# mega128.net
KiCad netlist of a schematic drawn in EAGLE
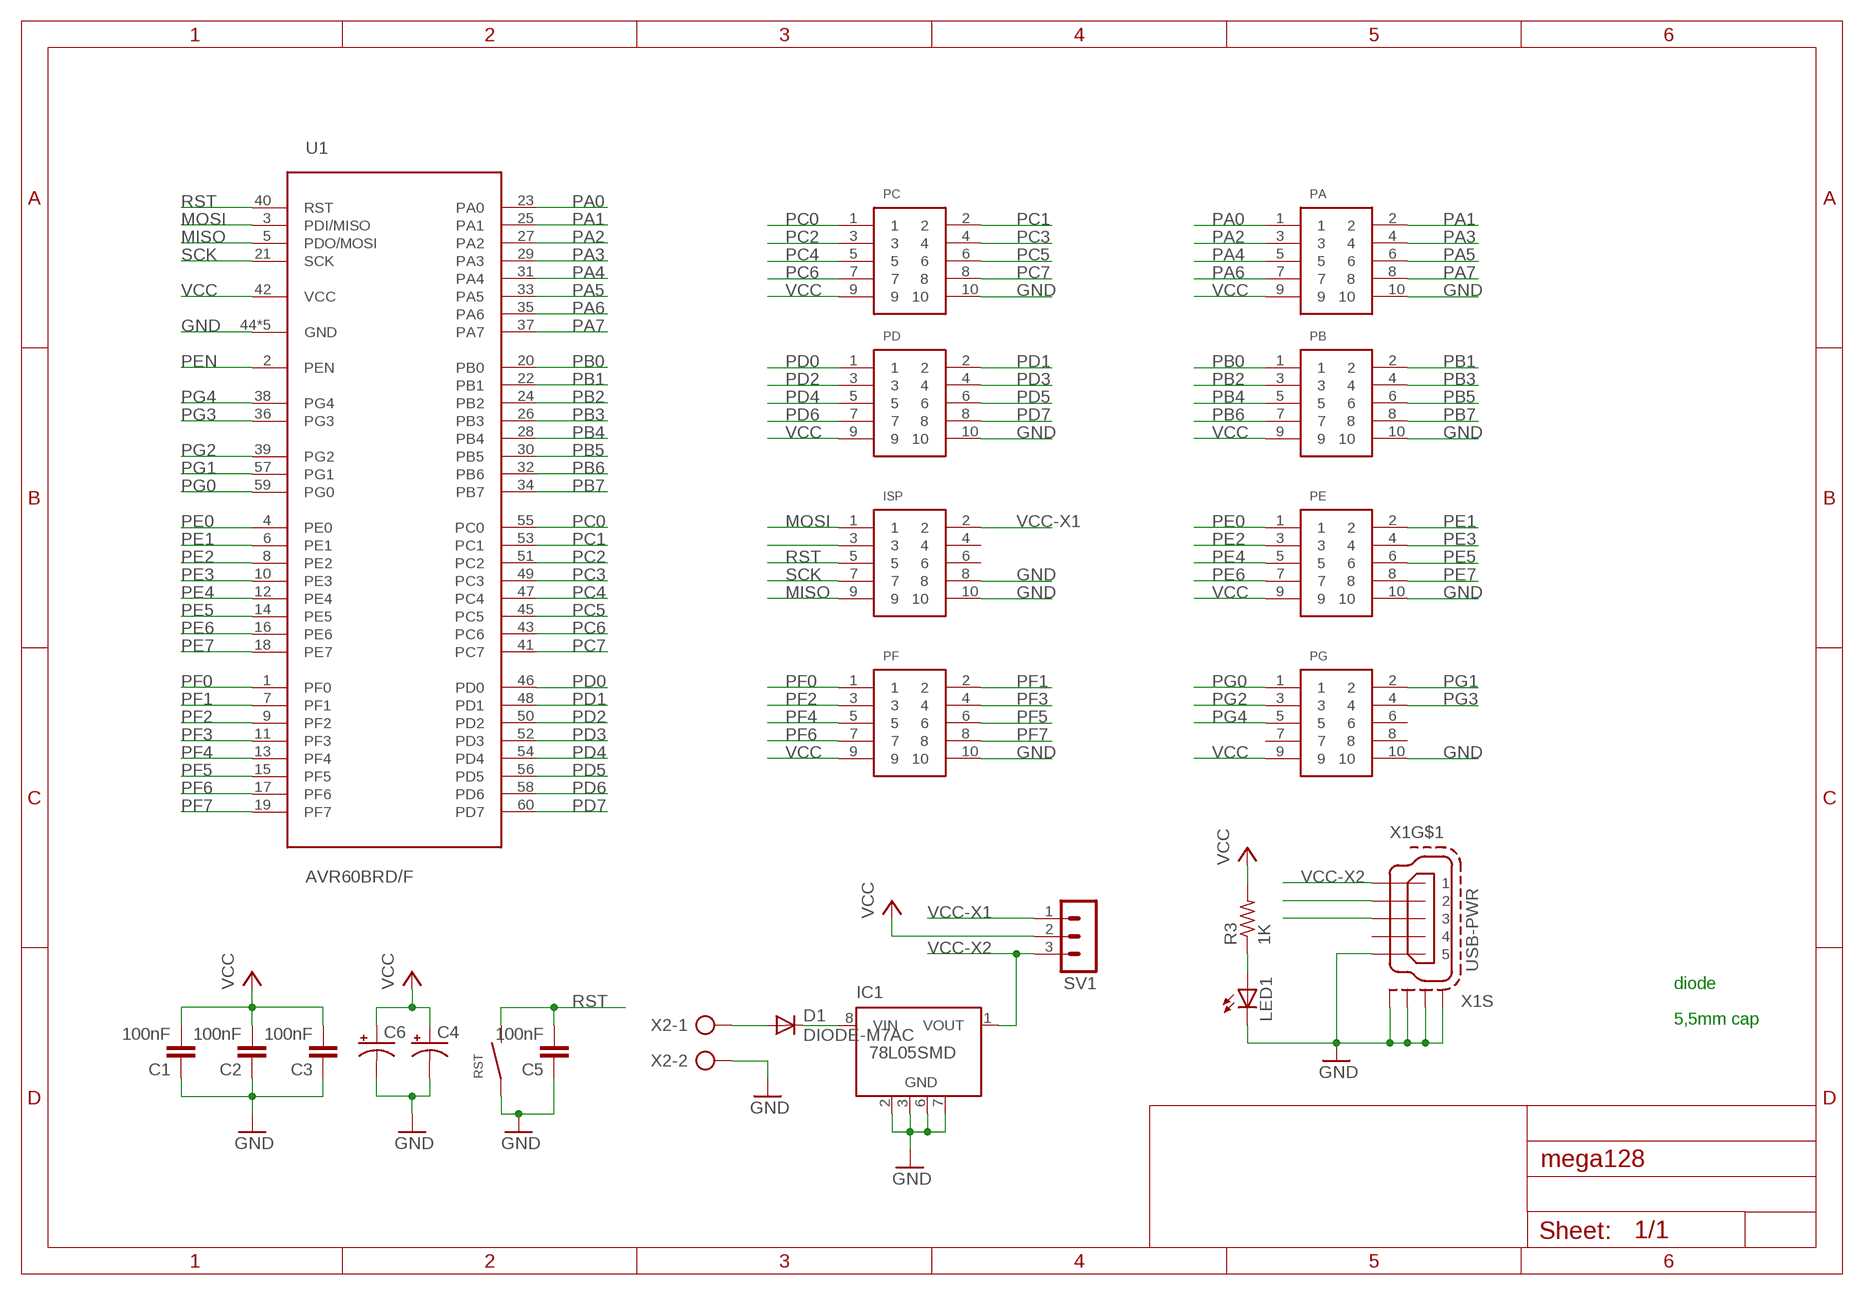
[diagram p0: schematic, sheet 1]

(export (version "E")
  (design (tool "Eeschema 10.0.6"))
  (components
    (comp (ref "C1")
      (value "100nF")
      (footprint "eagle-import:C0805")
      (libsource (lib "eagle-import") (part "C-EUC0805"))
    )
    (comp (ref "C2")
      (value "100nF")
      (footprint "eagle-import:C0805")
      (libsource (lib "eagle-import") (part "C-EUC0805"))
    )
    (comp (ref "C3")
      (value "100nF")
      (footprint "eagle-import:C0805")
      (libsource (lib "eagle-import") (part "C-EUC0805"))
    )
    (comp (ref "C4")
      (value "CPOL-US085CS-1AR")
      (footprint "eagle-import:085CS_1AR")
      (libsource (lib "eagle-import") (part "CPOL-US085CS-1AR"))
    )
    (comp (ref "C5")
      (value "100nF")
      (footprint "eagle-import:C0805")
      (libsource (lib "eagle-import") (part "C-EUC0805"))
    )
    (comp (ref "C6")
      (value "CPOL-US085CS-1AR")
      (footprint "eagle-import:085CS_1AR")
      (libsource (lib "eagle-import") (part "CPOL-US085CS-1AR"))
    )
    (comp (ref "D1")
      (value "DIODE-M7AC")
      (footprint "eagle-import:M7")
      (libsource (lib "eagle-import") (part "DIODE-M7AC"))
    )
    (comp (ref "IC1")
      (value "78L05SMD")
      (footprint "eagle-import:SO08")
      (libsource (lib "eagle-import") (part "78LSMD05"))
    )
    (comp (ref "ISP")
      (value "IDC-SOCK")
      (footprint "eagle-import:IDC-SOCK")
      (libsource (lib "eagle-import") (part "IDC-SOCK"))
    )
    (comp (ref "LED1")
      (value "LEDSML0805")
      (footprint "eagle-import:SML0805")
      (libsource (lib "eagle-import") (part "LEDSML0805"))
    )
    (comp (ref "PA")
      (value "IDC-SOCK")
      (footprint "eagle-import:IDC-SOCK")
      (libsource (lib "eagle-import") (part "IDC-SOCK"))
    )
    (comp (ref "PB")
      (value "IDC-SOCK")
      (footprint "eagle-import:IDC-SOCK")
      (libsource (lib "eagle-import") (part "IDC-SOCK"))
    )
    (comp (ref "PC")
      (value "IDC-SOCK")
      (footprint "eagle-import:IDC-SOCK")
      (libsource (lib "eagle-import") (part "IDC-SOCK"))
    )
    (comp (ref "PD")
      (value "IDC-SOCK")
      (footprint "eagle-import:IDC-SOCK")
      (libsource (lib "eagle-import") (part "IDC-SOCK"))
    )
    (comp (ref "PE")
      (value "IDC-SOCK")
      (footprint "eagle-import:IDC-SOCK")
      (libsource (lib "eagle-import") (part "IDC-SOCK"))
    )
    (comp (ref "PF")
      (value "IDC-SOCK")
      (footprint "eagle-import:IDC-SOCK")
      (libsource (lib "eagle-import") (part "IDC-SOCK"))
    )
    (comp (ref "PG")
      (value "IDC-SOCK")
      (footprint "eagle-import:IDC-SOCK")
      (libsource (lib "eagle-import") (part "IDC-SOCK"))
    )
    (comp (ref "R3")
      (value "1K")
      (footprint "eagle-import:R0805")
      (libsource (lib "eagle-import") (part "R-US_R0805"))
    )
    (comp (ref "RST")
      (value "SMD-BTN")
      (footprint "eagle-import:SMD-BTN")
      (libsource (lib "eagle-import") (part "SMD-BTN"))
    )
    (comp (ref "SV1")
      (value "MA03-1")
      (footprint "eagle-import:MA03-1")
      (libsource (lib "eagle-import") (part "MA03-1"))
    )
    (comp (ref "U1")
      (value "AVR60BRD/F")
      (footprint "eagle-import:AVR60-BRD")
      (libsource (lib "eagle-import") (part "AVR60BRD/F"))
    )
    (comp (ref "X1")
      (value "USB-PWR")
      (footprint "eagle-import:32005-201")
      (libsource (lib "eagle-import") (part "MINI-USB-SCHIELD-32005-201"))
    )
    (comp (ref "X2")
      (value "AK300/2")
      (footprint "eagle-import:AK300_2")
      (libsource (lib "eagle-import") (part "AK300/2"))
    )
  )
  (nets
    (net (code "1") (name "/MISO") (class "Default")
      (node (ref "ISP") (pin "9") (pinfunction "9_9") (pintype "bidirectional"))
      (node (ref "U1") (pin "5") (pinfunction "PDO/MOSI_5") (pintype "bidirectional"))
    )
    (net (code "2") (name "/MOSI") (class "Default")
      (node (ref "ISP") (pin "1") (pinfunction "1_1") (pintype "bidirectional"))
      (node (ref "U1") (pin "3") (pinfunction "PDI/MISO_3") (pintype "bidirectional"))
    )
    (net (code "3") (name "/PA0") (class "Default")
      (node (ref "PA") (pin "1") (pinfunction "1_1") (pintype "bidirectional"))
      (node (ref "U1") (pin "23") (pinfunction "PA0_23") (pintype "bidirectional"))
    )
    (net (code "4") (name "/PA1") (class "Default")
      (node (ref "PA") (pin "2") (pinfunction "2_2") (pintype "bidirectional"))
      (node (ref "U1") (pin "25") (pinfunction "PA1_25") (pintype "bidirectional"))
    )
    (net (code "5") (name "/PA2") (class "Default")
      (node (ref "PA") (pin "3") (pinfunction "3_3") (pintype "bidirectional"))
      (node (ref "U1") (pin "27") (pinfunction "PA2_27") (pintype "bidirectional"))
    )
    (net (code "6") (name "/PA3") (class "Default")
      (node (ref "PA") (pin "4") (pinfunction "4_4") (pintype "bidirectional"))
      (node (ref "U1") (pin "29") (pinfunction "PA3_29") (pintype "bidirectional"))
    )
    (net (code "7") (name "/PA4") (class "Default")
      (node (ref "PA") (pin "5") (pinfunction "5_5") (pintype "bidirectional"))
      (node (ref "U1") (pin "31") (pinfunction "PA4_31") (pintype "bidirectional"))
    )
    (net (code "8") (name "/PA5") (class "Default")
      (node (ref "PA") (pin "6") (pinfunction "6_6") (pintype "bidirectional"))
      (node (ref "U1") (pin "33") (pinfunction "PA5_33") (pintype "bidirectional"))
    )
    (net (code "9") (name "/PA6") (class "Default")
      (node (ref "PA") (pin "7") (pinfunction "7_7") (pintype "bidirectional"))
      (node (ref "U1") (pin "35") (pinfunction "PA6_35") (pintype "bidirectional"))
    )
    (net (code "10") (name "/PA7") (class "Default")
      (node (ref "PA") (pin "8") (pinfunction "8_8") (pintype "bidirectional"))
      (node (ref "U1") (pin "37") (pinfunction "PA7_37") (pintype "bidirectional"))
    )
    (net (code "11") (name "/PB0") (class "Default")
      (node (ref "PB") (pin "1") (pinfunction "1_1") (pintype "bidirectional"))
      (node (ref "U1") (pin "20") (pinfunction "PB0_20") (pintype "bidirectional"))
    )
    (net (code "12") (name "/PB1") (class "Default")
      (node (ref "PB") (pin "2") (pinfunction "2_2") (pintype "bidirectional"))
      (node (ref "U1") (pin "22") (pinfunction "PB1_22") (pintype "bidirectional"))
    )
    (net (code "13") (name "/PB2") (class "Default")
      (node (ref "PB") (pin "3") (pinfunction "3_3") (pintype "bidirectional"))
      (node (ref "U1") (pin "24") (pinfunction "PB2_24") (pintype "bidirectional"))
    )
    (net (code "14") (name "/PB3") (class "Default")
      (node (ref "PB") (pin "4") (pinfunction "4_4") (pintype "bidirectional"))
      (node (ref "U1") (pin "26") (pinfunction "PB3_26") (pintype "bidirectional"))
    )
    (net (code "15") (name "/PB4") (class "Default")
      (node (ref "PB") (pin "5") (pinfunction "5_5") (pintype "bidirectional"))
      (node (ref "U1") (pin "28") (pinfunction "PB4_28") (pintype "bidirectional"))
    )
    (net (code "16") (name "/PB5") (class "Default")
      (node (ref "PB") (pin "6") (pinfunction "6_6") (pintype "bidirectional"))
      (node (ref "U1") (pin "30") (pinfunction "PB5_30") (pintype "bidirectional"))
    )
    (net (code "17") (name "/PB6") (class "Default")
      (node (ref "PB") (pin "7") (pinfunction "7_7") (pintype "bidirectional"))
      (node (ref "U1") (pin "32") (pinfunction "PB6_32") (pintype "bidirectional"))
    )
    (net (code "18") (name "/PB7") (class "Default")
      (node (ref "PB") (pin "8") (pinfunction "8_8") (pintype "bidirectional"))
      (node (ref "U1") (pin "34") (pinfunction "PB7_34") (pintype "bidirectional"))
    )
    (net (code "19") (name "/PC0") (class "Default")
      (node (ref "PC") (pin "1") (pinfunction "1_1") (pintype "bidirectional"))
      (node (ref "U1") (pin "55") (pinfunction "PC0_55") (pintype "bidirectional"))
    )
    (net (code "20") (name "/PC1") (class "Default")
      (node (ref "PC") (pin "2") (pinfunction "2_2") (pintype "bidirectional"))
      (node (ref "U1") (pin "53") (pinfunction "PC1_53") (pintype "bidirectional"))
    )
    (net (code "21") (name "/PC2") (class "Default")
      (node (ref "PC") (pin "3") (pinfunction "3_3") (pintype "bidirectional"))
      (node (ref "U1") (pin "51") (pinfunction "PC2_51") (pintype "bidirectional"))
    )
    (net (code "22") (name "/PC3") (class "Default")
      (node (ref "PC") (pin "4") (pinfunction "4_4") (pintype "bidirectional"))
      (node (ref "U1") (pin "49") (pinfunction "PC3_49") (pintype "bidirectional"))
    )
    (net (code "23") (name "/PC4") (class "Default")
      (node (ref "PC") (pin "5") (pinfunction "5_5") (pintype "bidirectional"))
      (node (ref "U1") (pin "47") (pinfunction "PC4_47") (pintype "bidirectional"))
    )
    (net (code "24") (name "/PC5") (class "Default")
      (node (ref "PC") (pin "6") (pinfunction "6_6") (pintype "bidirectional"))
      (node (ref "U1") (pin "45") (pinfunction "PC5_45") (pintype "bidirectional"))
    )
    (net (code "25") (name "/PC6") (class "Default")
      (node (ref "PC") (pin "7") (pinfunction "7_7") (pintype "bidirectional"))
      (node (ref "U1") (pin "43") (pinfunction "PC6_43") (pintype "bidirectional"))
    )
    (net (code "26") (name "/PC7") (class "Default")
      (node (ref "PC") (pin "8") (pinfunction "8_8") (pintype "bidirectional"))
      (node (ref "U1") (pin "41") (pinfunction "PC7_41") (pintype "bidirectional"))
    )
    (net (code "27") (name "/PD0") (class "Default")
      (node (ref "PD") (pin "1") (pinfunction "1_1") (pintype "bidirectional"))
      (node (ref "U1") (pin "46") (pinfunction "PD0_46") (pintype "bidirectional"))
    )
    (net (code "28") (name "/PD1") (class "Default")
      (node (ref "PD") (pin "2") (pinfunction "2_2") (pintype "bidirectional"))
      (node (ref "U1") (pin "48") (pinfunction "PD1_48") (pintype "bidirectional"))
    )
    (net (code "29") (name "/PD2") (class "Default")
      (node (ref "PD") (pin "3") (pinfunction "3_3") (pintype "bidirectional"))
      (node (ref "U1") (pin "50") (pinfunction "PD2_50") (pintype "bidirectional"))
    )
    (net (code "30") (name "/PD3") (class "Default")
      (node (ref "PD") (pin "4") (pinfunction "4_4") (pintype "bidirectional"))
      (node (ref "U1") (pin "52") (pinfunction "PD3_52") (pintype "bidirectional"))
    )
    (net (code "31") (name "/PD4") (class "Default")
      (node (ref "PD") (pin "5") (pinfunction "5_5") (pintype "bidirectional"))
      (node (ref "U1") (pin "54") (pinfunction "PD4_54") (pintype "bidirectional"))
    )
    (net (code "32") (name "/PD5") (class "Default")
      (node (ref "PD") (pin "6") (pinfunction "6_6") (pintype "bidirectional"))
      (node (ref "U1") (pin "56") (pinfunction "PD5_56") (pintype "bidirectional"))
    )
    (net (code "33") (name "/PD6") (class "Default")
      (node (ref "PD") (pin "7") (pinfunction "7_7") (pintype "bidirectional"))
      (node (ref "U1") (pin "58") (pinfunction "PD6_58") (pintype "bidirectional"))
    )
    (net (code "34") (name "/PD7") (class "Default")
      (node (ref "PD") (pin "8") (pinfunction "8_8") (pintype "bidirectional"))
      (node (ref "U1") (pin "60") (pinfunction "PD7_60") (pintype "bidirectional"))
    )
    (net (code "35") (name "/PE0") (class "Default")
      (node (ref "PE") (pin "1") (pinfunction "1_1") (pintype "bidirectional"))
      (node (ref "U1") (pin "4") (pinfunction "PE0_4") (pintype "bidirectional"))
    )
    (net (code "36") (name "/PE1") (class "Default")
      (node (ref "PE") (pin "2") (pinfunction "2_2") (pintype "bidirectional"))
      (node (ref "U1") (pin "6") (pinfunction "PE1_6") (pintype "bidirectional"))
    )
    (net (code "37") (name "/PE2") (class "Default")
      (node (ref "PE") (pin "3") (pinfunction "3_3") (pintype "bidirectional"))
      (node (ref "U1") (pin "8") (pinfunction "PE2_8") (pintype "bidirectional"))
    )
    (net (code "38") (name "/PE3") (class "Default")
      (node (ref "PE") (pin "4") (pinfunction "4_4") (pintype "bidirectional"))
      (node (ref "U1") (pin "10") (pinfunction "PE3_10") (pintype "bidirectional"))
    )
    (net (code "39") (name "/PE4") (class "Default")
      (node (ref "PE") (pin "5") (pinfunction "5_5") (pintype "bidirectional"))
      (node (ref "U1") (pin "12") (pinfunction "PE4_12") (pintype "bidirectional"))
    )
    (net (code "40") (name "/PE5") (class "Default")
      (node (ref "PE") (pin "6") (pinfunction "6_6") (pintype "bidirectional"))
      (node (ref "U1") (pin "14") (pinfunction "PE5_14") (pintype "bidirectional"))
    )
    (net (code "41") (name "/PE6") (class "Default")
      (node (ref "PE") (pin "7") (pinfunction "7_7") (pintype "bidirectional"))
      (node (ref "U1") (pin "16") (pinfunction "PE6_16") (pintype "bidirectional"))
    )
    (net (code "42") (name "/PE7") (class "Default")
      (node (ref "PE") (pin "8") (pinfunction "8_8") (pintype "bidirectional"))
      (node (ref "U1") (pin "18") (pinfunction "PE7_18") (pintype "bidirectional"))
    )
    (net (code "43") (name "/PEN") (class "Default")
      (node (ref "U1") (pin "2") (pinfunction "PEN_2") (pintype "bidirectional"))
    )
    (net (code "44") (name "/PF0") (class "Default")
      (node (ref "PF") (pin "1") (pinfunction "1_1") (pintype "bidirectional"))
      (node (ref "U1") (pin "1") (pinfunction "PF0_1") (pintype "bidirectional"))
    )
    (net (code "45") (name "/PF1") (class "Default")
      (node (ref "PF") (pin "2") (pinfunction "2_2") (pintype "bidirectional"))
      (node (ref "U1") (pin "7") (pinfunction "PF1_7") (pintype "bidirectional"))
    )
    (net (code "46") (name "/PF2") (class "Default")
      (node (ref "PF") (pin "3") (pinfunction "3_3") (pintype "bidirectional"))
      (node (ref "U1") (pin "9") (pinfunction "PF2_9") (pintype "bidirectional"))
    )
    (net (code "47") (name "/PF3") (class "Default")
      (node (ref "PF") (pin "4") (pinfunction "4_4") (pintype "bidirectional"))
      (node (ref "U1") (pin "11") (pinfunction "PF3_11") (pintype "bidirectional"))
    )
    (net (code "48") (name "/PF4") (class "Default")
      (node (ref "PF") (pin "5") (pinfunction "5_5") (pintype "bidirectional"))
      (node (ref "U1") (pin "13") (pinfunction "PF4_13") (pintype "bidirectional"))
    )
    (net (code "49") (name "/PF5") (class "Default")
      (node (ref "PF") (pin "6") (pinfunction "6_6") (pintype "bidirectional"))
      (node (ref "U1") (pin "15") (pinfunction "PF5_15") (pintype "bidirectional"))
    )
    (net (code "50") (name "/PF6") (class "Default")
      (node (ref "PF") (pin "7") (pinfunction "7_7") (pintype "bidirectional"))
      (node (ref "U1") (pin "17") (pinfunction "PF6_17") (pintype "bidirectional"))
    )
    (net (code "51") (name "/PF7") (class "Default")
      (node (ref "PF") (pin "8") (pinfunction "8_8") (pintype "bidirectional"))
      (node (ref "U1") (pin "19") (pinfunction "PF7_19") (pintype "bidirectional"))
    )
    (net (code "52") (name "/PG0") (class "Default")
      (node (ref "PG") (pin "1") (pinfunction "1_1") (pintype "bidirectional"))
      (node (ref "U1") (pin "59") (pinfunction "PG0_59") (pintype "bidirectional"))
    )
    (net (code "53") (name "/PG1") (class "Default")
      (node (ref "PG") (pin "2") (pinfunction "2_2") (pintype "bidirectional"))
      (node (ref "U1") (pin "57") (pinfunction "PG1_57") (pintype "bidirectional"))
    )
    (net (code "54") (name "/PG2") (class "Default")
      (node (ref "PG") (pin "3") (pinfunction "3_3") (pintype "bidirectional"))
      (node (ref "U1") (pin "39") (pinfunction "PG2_39") (pintype "bidirectional"))
    )
    (net (code "55") (name "/PG3") (class "Default")
      (node (ref "PG") (pin "4") (pinfunction "4_4") (pintype "bidirectional"))
      (node (ref "U1") (pin "36") (pinfunction "PG3_36") (pintype "bidirectional"))
    )
    (net (code "56") (name "/PG4") (class "Default")
      (node (ref "PG") (pin "5") (pinfunction "5_5") (pintype "bidirectional"))
      (node (ref "U1") (pin "38") (pinfunction "PG4_38") (pintype "bidirectional"))
    )
    (net (code "57") (name "/RST") (class "Default")
      (node (ref "C5") (pin "2") (pinfunction "2_2") (pintype "passive"))
      (node (ref "ISP") (pin "5") (pinfunction "5_5") (pintype "bidirectional"))
      (node (ref "RST") (pin "2") (pinfunction "P$2_2") (pintype "bidirectional"))
      (node (ref "U1") (pin "40") (pinfunction "RST_40") (pintype "bidirectional"))
    )
    (net (code "58") (name "/SCK") (class "Default")
      (node (ref "ISP") (pin "7") (pinfunction "7_7") (pintype "bidirectional"))
      (node (ref "U1") (pin "21") (pinfunction "SCK_21") (pintype "bidirectional"))
    )
    (net (code "59") (name "/VCC-X1") (class "Default")
      (node (ref "ISP") (pin "2") (pinfunction "2_2") (pintype "bidirectional"))
      (node (ref "SV1") (pin "1") (pinfunction "1_1") (pintype "passive"))
    )
    (net (code "60") (name "/VCC-X2") (class "Default")
      (node (ref "IC1") (pin "1") (pinfunction "VOUT_1") (pintype "output"))
      (node (ref "SV1") (pin "3") (pinfunction "3_3") (pintype "passive"))
      (node (ref "X1") (pin "1") (pinfunction "1_1") (pintype "passive"))
    )
    (net (code "61") (name "GND") (class "Default")
      (node (ref "C1") (pin "1") (pinfunction "1_1") (pintype "passive"))
      (node (ref "C2") (pin "1") (pinfunction "1_1") (pintype "passive"))
      (node (ref "C3") (pin "1") (pinfunction "1_1") (pintype "passive"))
      (node (ref "C4") (pin "-") (pinfunction "-_-") (pintype "passive"))
      (node (ref "C5") (pin "1") (pinfunction "1_1") (pintype "passive"))
      (node (ref "C6") (pin "-") (pinfunction "-_-") (pintype "passive"))
      (node (ref "IC1") (pin "2") (pinfunction "GND_2") (pintype "power_in"))
      (node (ref "IC1") (pin "3") (pinfunction "GND_3") (pintype "power_in"))
      (node (ref "IC1") (pin "6") (pinfunction "GND_6") (pintype "power_in"))
      (node (ref "IC1") (pin "7") (pinfunction "GND_7") (pintype "power_in"))
      (node (ref "ISP") (pin "10") (pinfunction "10_10") (pintype "bidirectional"))
      (node (ref "ISP") (pin "8") (pinfunction "8_8") (pintype "bidirectional"))
      (node (ref "LED1") (pin "C") (pinfunction "C_C") (pintype "passive"))
      (node (ref "PA") (pin "10") (pinfunction "10_10") (pintype "bidirectional"))
      (node (ref "PB") (pin "10") (pinfunction "10_10") (pintype "bidirectional"))
      (node (ref "PC") (pin "10") (pinfunction "10_10") (pintype "bidirectional"))
      (node (ref "PD") (pin "10") (pinfunction "10_10") (pintype "bidirectional"))
      (node (ref "PE") (pin "10") (pinfunction "10_10") (pintype "bidirectional"))
      (node (ref "PF") (pin "10") (pinfunction "10_10") (pintype "bidirectional"))
      (node (ref "PG") (pin "10") (pinfunction "10_10") (pintype "bidirectional"))
      (node (ref "RST") (pin "1") (pinfunction "P$1_1") (pintype "bidirectional"))
      (node (ref "U1") (pin "44") (pinfunction "GND_44") (pintype "bidirectional"))
      (node (ref "U1") (pin "61") (pinfunction "GND_61") (pintype "bidirectional"))
      (node (ref "U1") (pin "62") (pinfunction "GND_62") (pintype "bidirectional"))
      (node (ref "U1") (pin "63") (pinfunction "GND_63") (pintype "bidirectional"))
      (node (ref "U1") (pin "64") (pinfunction "GND_64") (pintype "bidirectional"))
      (node (ref "X1") (pin "5") (pinfunction "5_5") (pintype "passive"))
      (node (ref "X1") (pin "M1") (pinfunction "S1_M1") (pintype "passive"))
      (node (ref "X1") (pin "M2") (pinfunction "S2_M2") (pintype "passive"))
      (node (ref "X1") (pin "M3") (pinfunction "S3_M3") (pintype "passive"))
      (node (ref "X1") (pin "M4") (pinfunction "S4_M4") (pintype "passive"))
      (node (ref "X2") (pin "2") (pinfunction "KL_2") (pintype "passive"))
    )
    (net (code "62") (name "Net-(D1-A)") (class "Default")
      (node (ref "D1") (pin "2") (pinfunction "A_2") (pintype "passive"))
      (node (ref "X2") (pin "1") (pinfunction "KL_1") (pintype "passive"))
    )
    (net (code "63") (name "Net-(D1-C)") (class "Default")
      (node (ref "D1") (pin "1") (pinfunction "C_1") (pintype "passive"))
      (node (ref "IC1") (pin "8") (pinfunction "VIN_8") (pintype "passive"))
    )
    (net (code "64") (name "Net-(LED1-PadA)") (class "Default")
      (node (ref "LED1") (pin "A") (pinfunction "A_A") (pintype "passive"))
      (node (ref "R3") (pin "1") (pinfunction "1_1") (pintype "passive"))
    )
    (net (code "65") (name "VCC") (class "Default")
      (node (ref "C1") (pin "2") (pinfunction "2_2") (pintype "passive"))
      (node (ref "C2") (pin "2") (pinfunction "2_2") (pintype "passive"))
      (node (ref "C3") (pin "2") (pinfunction "2_2") (pintype "passive"))
      (node (ref "C4") (pin "+") (pinfunction "+_+") (pintype "passive"))
      (node (ref "C6") (pin "+") (pinfunction "+_+") (pintype "passive"))
      (node (ref "PA") (pin "9") (pinfunction "9_9") (pintype "bidirectional"))
      (node (ref "PB") (pin "9") (pinfunction "9_9") (pintype "bidirectional"))
      (node (ref "PC") (pin "9") (pinfunction "9_9") (pintype "bidirectional"))
      (node (ref "PD") (pin "9") (pinfunction "9_9") (pintype "bidirectional"))
      (node (ref "PE") (pin "9") (pinfunction "9_9") (pintype "bidirectional"))
      (node (ref "PF") (pin "9") (pinfunction "9_9") (pintype "bidirectional"))
      (node (ref "PG") (pin "9") (pinfunction "9_9") (pintype "bidirectional"))
      (node (ref "R3") (pin "2") (pinfunction "2_2") (pintype "passive"))
      (node (ref "SV1") (pin "2") (pinfunction "2_2") (pintype "passive"))
      (node (ref "U1") (pin "42") (pinfunction "VCC_42") (pintype "bidirectional"))
    )
    (net (code "66") (name "unconnected-(ISP-Pad3)") (class "Default")
      (node (ref "ISP") (pin "3") (pinfunction "3_3") (pintype "bidirectional"))
    )
    (net (code "67") (name "unconnected-(ISP-Pad4)") (class "Default")
      (node (ref "ISP") (pin "4") (pinfunction "4_4") (pintype "bidirectional"))
    )
    (net (code "68") (name "unconnected-(ISP-Pad6)") (class "Default")
      (node (ref "ISP") (pin "6") (pinfunction "6_6") (pintype "bidirectional"))
    )
    (net (code "69") (name "unconnected-(PG-Pad6)") (class "Default")
      (node (ref "PG") (pin "6") (pinfunction "6_6") (pintype "bidirectional"))
    )
    (net (code "70") (name "unconnected-(PG-Pad7)") (class "Default")
      (node (ref "PG") (pin "7") (pinfunction "7_7") (pintype "bidirectional"))
    )
    (net (code "71") (name "unconnected-(PG-Pad8)") (class "Default")
      (node (ref "PG") (pin "8") (pinfunction "8_8") (pintype "bidirectional"))
    )
    (net (code "72") (name "unconnected-(X1-Pad2)") (class "Default")
      (node (ref "X1") (pin "2") (pinfunction "2_2") (pintype "passive"))
    )
    (net (code "73") (name "unconnected-(X1-Pad3)") (class "Default")
      (node (ref "X1") (pin "3") (pinfunction "3_3") (pintype "passive"))
    )
    (net (code "74") (name "unconnected-(X1-Pad4)") (class "Default")
      (node (ref "X1") (pin "4") (pinfunction "4_4") (pintype "passive"))
    )
  )
)
